# MT9V034.net
KiCad netlist of a schematic drawn in EAGLE
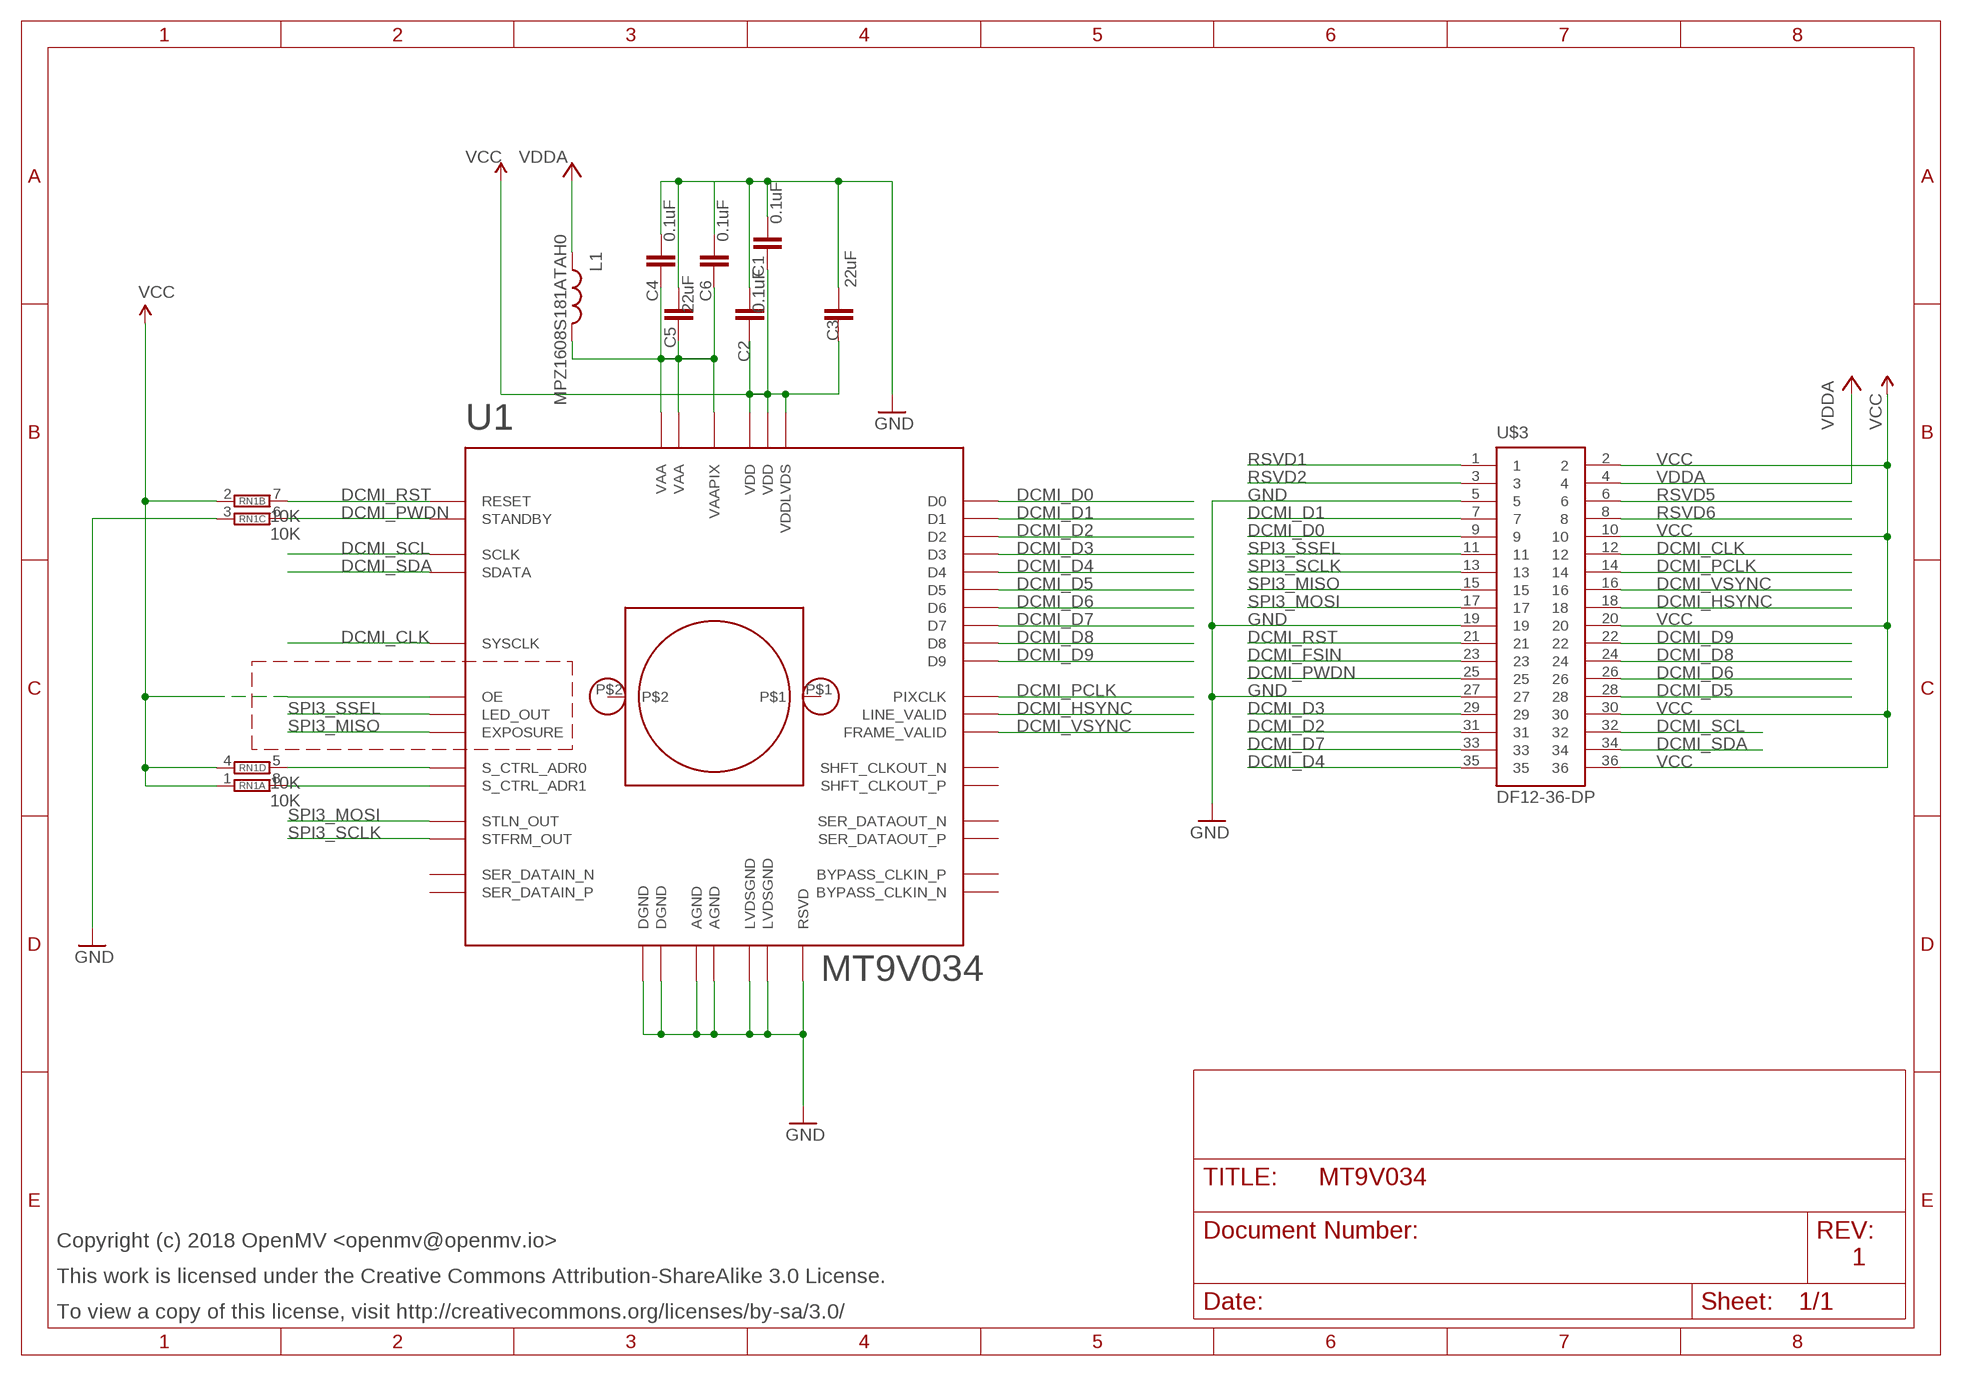
[diagram p0: schematic, sheet 1]

(export (version "E")
  (design (tool "Eeschema 10.0.6"))
  (components
    (comp (ref "C1")
      (value "0.1uF")
      (footprint "eagle-import:0402-CAP")
      (libsource (lib "eagle-import") (part "CAP0402-CAP"))
    )
    (comp (ref "C2")
      (value "0.1uF")
      (footprint "eagle-import:0402-CAP")
      (libsource (lib "eagle-import") (part "CAP0402-CAP"))
    )
    (comp (ref "C3")
      (value "22uF")
      (footprint "eagle-import:0805")
      (libsource (lib "eagle-import") (part "CAP0805"))
    )
    (comp (ref "C4")
      (value "0.1uF")
      (footprint "eagle-import:0402-CAP")
      (libsource (lib "eagle-import") (part "CAP0402-CAP"))
    )
    (comp (ref "C5")
      (value "22uF")
      (footprint "eagle-import:0805")
      (libsource (lib "eagle-import") (part "CAP0805"))
    )
    (comp (ref "C6")
      (value "0.1uF")
      (footprint "eagle-import:0402-CAP")
      (libsource (lib "eagle-import") (part "CAP0402-CAP"))
    )
    (comp (ref "L1")
      (value "MPZ1608S181ATAH0")
      (footprint "eagle-import:0603")
      (libsource (lib "eagle-import") (part "INDUCTOR0603"))
    )
    (comp (ref "LM1")
      (value "LENSMOUNT20MM")
      (footprint "eagle-import:LENSMOUNT-20MM")
      (libsource (lib "eagle-import") (part "LENSMOUNT20MM"))
    )
    (comp (ref "RN1")
      (value "10K")
      (footprint "eagle-import:EXBV8V")
      (fields (field (name "OC_FARNELL") "unknown") (field (name "OC_NEWARK") "unknown"))
      (libsource (lib "eagle-import") (part "4R-NEXBV8V"))
    )
    (comp (ref "U$3")
      (value "DF12-36-DP")
      (footprint "eagle-import:DF12-36-DP")
      (libsource (lib "eagle-import") (part "DF12-36-DP"))
    )
    (comp (ref "U1")
      (value "MT9V034")
      (footprint "eagle-import:CLCC-48")
      (libsource (lib "eagle-import") (part "MT9V032"))
    )
  )
  (nets
    (net (code "1") (name "/DCMI_CLK") (class "Default")
      (node (ref "U$3") (pin "12") (pinfunction "12_12") (pintype "bidirectional"))
      (node (ref "U1") (pin "P$47") (pinfunction "SYSCLK_P$47") (pintype "bidirectional"))
    )
    (net (code "2") (name "/DCMI_D0") (class "Default")
      (node (ref "U$3") (pin "9") (pinfunction "9_9") (pintype "bidirectional"))
      (node (ref "U1") (pin "P$45") (pinfunction "D0_P$45") (pintype "bidirectional"))
    )
    (net (code "3") (name "/DCMI_D1") (class "Default")
      (node (ref "U$3") (pin "7") (pinfunction "7_7") (pintype "bidirectional"))
      (node (ref "U1") (pin "P$44") (pinfunction "D1_P$44") (pintype "bidirectional"))
    )
    (net (code "4") (name "/DCMI_D2") (class "Default")
      (node (ref "U$3") (pin "31") (pinfunction "31_31") (pintype "bidirectional"))
      (node (ref "U1") (pin "P$43") (pinfunction "D2_P$43") (pintype "bidirectional"))
    )
    (net (code "5") (name "/DCMI_D3") (class "Default")
      (node (ref "U$3") (pin "29") (pinfunction "29_29") (pintype "bidirectional"))
      (node (ref "U1") (pin "P$42") (pinfunction "D3_P$42") (pintype "bidirectional"))
    )
    (net (code "6") (name "/DCMI_D4") (class "Default")
      (node (ref "U$3") (pin "35") (pinfunction "35_35") (pintype "bidirectional"))
      (node (ref "U1") (pin "P$41") (pinfunction "D4_P$41") (pintype "bidirectional"))
    )
    (net (code "7") (name "/DCMI_D5") (class "Default")
      (node (ref "U$3") (pin "28") (pinfunction "28_28") (pintype "bidirectional"))
      (node (ref "U1") (pin "P$15") (pinfunction "D5_P$15") (pintype "bidirectional"))
    )
    (net (code "8") (name "/DCMI_D6") (class "Default")
      (node (ref "U$3") (pin "26") (pinfunction "26_26") (pintype "bidirectional"))
      (node (ref "U1") (pin "P$16") (pinfunction "D6_P$16") (pintype "bidirectional"))
    )
    (net (code "9") (name "/DCMI_D7") (class "Default")
      (node (ref "U$3") (pin "33") (pinfunction "33_33") (pintype "bidirectional"))
      (node (ref "U1") (pin "P$17") (pinfunction "D7_P$17") (pintype "bidirectional"))
    )
    (net (code "10") (name "/DCMI_D8") (class "Default")
      (node (ref "U$3") (pin "24") (pinfunction "24_24") (pintype "bidirectional"))
      (node (ref "U1") (pin "P$18") (pinfunction "D8_P$18") (pintype "bidirectional"))
    )
    (net (code "11") (name "/DCMI_D9") (class "Default")
      (node (ref "U$3") (pin "22") (pinfunction "22_22") (pintype "bidirectional"))
      (node (ref "U1") (pin "P$19") (pinfunction "D9_P$19") (pintype "bidirectional"))
    )
    (net (code "12") (name "/DCMI_FSIN") (class "Default")
      (node (ref "U$3") (pin "23") (pinfunction "23_23") (pintype "bidirectional"))
    )
    (net (code "13") (name "/DCMI_HSYNC") (class "Default")
      (node (ref "U$3") (pin "18") (pinfunction "18_18") (pintype "bidirectional"))
      (node (ref "U1") (pin "P$20") (pinfunction "LINE_VALID_P$20") (pintype "bidirectional"))
    )
    (net (code "14") (name "/DCMI_PCLK") (class "Default")
      (node (ref "U$3") (pin "14") (pinfunction "14_14") (pintype "bidirectional"))
      (node (ref "U1") (pin "P$46") (pinfunction "PIXCLK_P$46") (pintype "bidirectional"))
    )
    (net (code "15") (name "/DCMI_PWDN") (class "Default")
      (node (ref "RN1") (pin "6") (pinfunction "2_6") (pintype "passive"))
      (node (ref "U$3") (pin "25") (pinfunction "25_25") (pintype "bidirectional"))
      (node (ref "U1") (pin "P$33") (pinfunction "STANDBY_P$33") (pintype "bidirectional"))
    )
    (net (code "16") (name "/DCMI_RST") (class "Default")
      (node (ref "RN1") (pin "7") (pinfunction "2_7") (pintype "passive"))
      (node (ref "U$3") (pin "21") (pinfunction "21_21") (pintype "bidirectional"))
      (node (ref "U1") (pin "P$32") (pinfunction "RESET_P$32") (pintype "bidirectional"))
    )
    (net (code "17") (name "/DCMI_SCL") (class "Default")
      (node (ref "U$3") (pin "32") (pinfunction "32_32") (pintype "bidirectional"))
      (node (ref "U1") (pin "P$25") (pinfunction "SCLK_P$25") (pintype "bidirectional"))
    )
    (net (code "18") (name "/DCMI_SDA") (class "Default")
      (node (ref "U$3") (pin "34") (pinfunction "34_34") (pintype "bidirectional"))
      (node (ref "U1") (pin "P$24") (pinfunction "SDATA_P$24") (pintype "bidirectional"))
    )
    (net (code "19") (name "/DCMI_VSYNC") (class "Default")
      (node (ref "U$3") (pin "16") (pinfunction "16_16") (pintype "bidirectional"))
      (node (ref "U1") (pin "P$21") (pinfunction "FRAME_VALID_P$21") (pintype "bidirectional"))
    )
    (net (code "20") (name "/P$1") (class "Default")
      (node (ref "LM1") (pin "P$1") (pinfunction "P$1_P$1") (pintype "power_in"))
    )
    (net (code "21") (name "/P$2") (class "Default")
      (node (ref "LM1") (pin "P$2") (pinfunction "P$2_P$2") (pintype "power_in"))
    )
    (net (code "22") (name "/RSVD1") (class "Default")
      (node (ref "U$3") (pin "1") (pinfunction "1_1") (pintype "bidirectional"))
    )
    (net (code "23") (name "/RSVD2") (class "Default")
      (node (ref "U$3") (pin "3") (pinfunction "3_3") (pintype "bidirectional"))
    )
    (net (code "24") (name "/RSVD5") (class "Default")
      (node (ref "U$3") (pin "6") (pinfunction "6_6") (pintype "bidirectional"))
    )
    (net (code "25") (name "/RSVD6") (class "Default")
      (node (ref "U$3") (pin "8") (pinfunction "8_8") (pintype "bidirectional"))
    )
    (net (code "26") (name "/SPI3_MISO") (class "Default")
      (node (ref "U$3") (pin "15") (pinfunction "15_15") (pintype "bidirectional"))
      (node (ref "U1") (pin "P$23") (pinfunction "EXPOSURE_P$23") (pintype "bidirectional"))
    )
    (net (code "27") (name "/SPI3_MOSI") (class "Default")
      (node (ref "U$3") (pin "17") (pinfunction "17_17") (pintype "bidirectional"))
      (node (ref "U1") (pin "P$22") (pinfunction "STLN_OUT_P$22") (pintype "bidirectional"))
    )
    (net (code "28") (name "/SPI3_SCLK") (class "Default")
      (node (ref "U$3") (pin "13") (pinfunction "13_13") (pintype "bidirectional"))
      (node (ref "U1") (pin "P$26") (pinfunction "STFRM_OUT_P$26") (pintype "bidirectional"))
    )
    (net (code "29") (name "/SPI3_SSEL") (class "Default")
      (node (ref "U$3") (pin "11") (pinfunction "11_11") (pintype "bidirectional"))
      (node (ref "U1") (pin "P$27") (pinfunction "LED_OUT_P$27") (pintype "bidirectional"))
    )
    (net (code "30") (name "GND") (class "Default")
      (node (ref "C1") (pin "2") (pinfunction "2_2") (pintype "passive"))
      (node (ref "C2") (pin "2") (pinfunction "2_2") (pintype "passive"))
      (node (ref "C3") (pin "1") (pinfunction "1_1") (pintype "passive"))
      (node (ref "C4") (pin "2") (pinfunction "2_2") (pintype "passive"))
      (node (ref "C5") (pin "1") (pinfunction "1_1") (pintype "passive"))
      (node (ref "C6") (pin "2") (pinfunction "2_2") (pintype "passive"))
      (node (ref "RN1") (pin "3") (pinfunction "1_3") (pintype "passive"))
      (node (ref "U$3") (pin "19") (pinfunction "19_19") (pintype "bidirectional"))
      (node (ref "U$3") (pin "27") (pinfunction "27_27") (pintype "bidirectional"))
      (node (ref "U$3") (pin "5") (pinfunction "5_5") (pintype "bidirectional"))
      (node (ref "U1") (pin "P$12") (pinfunction "LVDSGND_P$12") (pintype "power_in"))
      (node (ref "U1") (pin "P$13") (pinfunction "DGND_P$13") (pintype "power_in"))
      (node (ref "U1") (pin "P$29") (pinfunction "RSVD_P$29") (pintype "power_in"))
      (node (ref "U1") (pin "P$34") (pinfunction "AGND_P$34") (pintype "power_in"))
      (node (ref "U1") (pin "P$38") (pinfunction "AGND_P$38") (pintype "power_in"))
      (node (ref "U1") (pin "P$48") (pinfunction "DGND_P$48") (pintype "power_in"))
      (node (ref "U1") (pin "P$7") (pinfunction "LVDSGND_P$7") (pintype "power_in"))
    )
    (net (code "31") (name "Net-(RN1A-2)") (class "Default")
      (node (ref "RN1") (pin "8") (pinfunction "2_8") (pintype "passive"))
      (node (ref "U1") (pin "P$31") (pinfunction "S_CTRL_ADR1_P$31") (pintype "bidirectional"))
    )
    (net (code "32") (name "Net-(RN1D-2)") (class "Default")
      (node (ref "RN1") (pin "5") (pinfunction "2_5") (pintype "passive"))
      (node (ref "U1") (pin "P$30") (pinfunction "S_CTRL_ADR0_P$30") (pintype "bidirectional"))
    )
    (net (code "33") (name "Net-(U1-VAAPIX)") (class "Default")
      (node (ref "C4") (pin "1") (pinfunction "1_1") (pintype "passive"))
      (node (ref "C5") (pin "2") (pinfunction "2_2") (pintype "passive"))
      (node (ref "C6") (pin "1") (pinfunction "1_1") (pintype "passive"))
      (node (ref "L1") (pin "2") (pinfunction "2_2") (pintype "passive"))
      (node (ref "U1") (pin "P$35") (pinfunction "VAA_P$35") (pintype "power_in"))
      (node (ref "U1") (pin "P$39") (pinfunction "VAA_P$39") (pintype "power_in"))
      (node (ref "U1") (pin "P$40") (pinfunction "VAAPIX_P$40") (pintype "power_in"))
    )
    (net (code "34") (name "VCC") (class "Default")
      (node (ref "C1") (pin "1") (pinfunction "1_1") (pintype "passive"))
      (node (ref "C2") (pin "1") (pinfunction "1_1") (pintype "passive"))
      (node (ref "C3") (pin "2") (pinfunction "2_2") (pintype "passive"))
      (node (ref "RN1") (pin "1") (pinfunction "1_1") (pintype "passive"))
      (node (ref "RN1") (pin "2") (pinfunction "1_2") (pintype "passive"))
      (node (ref "RN1") (pin "4") (pinfunction "1_4") (pintype "passive"))
      (node (ref "U$3") (pin "10") (pinfunction "10_10") (pintype "bidirectional"))
      (node (ref "U$3") (pin "2") (pinfunction "2_2") (pintype "bidirectional"))
      (node (ref "U$3") (pin "20") (pinfunction "20_20") (pintype "bidirectional"))
      (node (ref "U$3") (pin "30") (pinfunction "30_30") (pintype "bidirectional"))
      (node (ref "U$3") (pin "36") (pinfunction "36_36") (pintype "bidirectional"))
      (node (ref "U1") (pin "P$1") (pinfunction "VDD_P$1") (pintype "power_in"))
      (node (ref "U1") (pin "P$14") (pinfunction "VDD_P$14") (pintype "power_in"))
      (node (ref "U1") (pin "P$28") (pinfunction "OE_P$28") (pintype "bidirectional"))
      (node (ref "U1") (pin "P$6") (pinfunction "VDDLVDS_P$6") (pintype "power_in"))
    )
    (net (code "35") (name "VDDA") (class "Default")
      (node (ref "L1") (pin "1") (pinfunction "1_1") (pintype "passive"))
      (node (ref "U$3") (pin "4") (pinfunction "4_4") (pintype "bidirectional"))
    )
    (net (code "36") (name "unconnected-(U1-BYPASS_CLKIN_N-PadP$8)") (class "Default")
      (node (ref "U1") (pin "P$8") (pinfunction "BYPASS_CLKIN_N_P$8") (pintype "bidirectional"))
    )
    (net (code "37") (name "unconnected-(U1-BYPASS_CLKIN_P-PadP$9)") (class "Default")
      (node (ref "U1") (pin "P$9") (pinfunction "BYPASS_CLKIN_P_P$9") (pintype "bidirectional"))
    )
    (net (code "38") (name "unconnected-(U1-SER_DATAIN_N-PadP$10)") (class "Default")
      (node (ref "U1") (pin "P$10") (pinfunction "SER_DATAIN_N_P$10") (pintype "bidirectional"))
    )
    (net (code "39") (name "unconnected-(U1-SER_DATAIN_P-PadP$11)") (class "Default")
      (node (ref "U1") (pin "P$11") (pinfunction "SER_DATAIN_P_P$11") (pintype "bidirectional"))
    )
    (net (code "40") (name "unconnected-(U1-SER_DATAOUT_N-PadP$5)") (class "Default")
      (node (ref "U1") (pin "P$5") (pinfunction "SER_DATAOUT_N_P$5") (pintype "bidirectional"))
    )
    (net (code "41") (name "unconnected-(U1-SER_DATAOUT_P-PadP$4)") (class "Default")
      (node (ref "U1") (pin "P$4") (pinfunction "SER_DATAOUT_P_P$4") (pintype "bidirectional"))
    )
    (net (code "42") (name "unconnected-(U1-SHFT_CLKOUT_N-PadP$2)") (class "Default")
      (node (ref "U1") (pin "P$2") (pinfunction "SHFT_CLKOUT_N_P$2") (pintype "bidirectional"))
    )
    (net (code "43") (name "unconnected-(U1-SHFT_CLKOUT_P-PadP$3)") (class "Default")
      (node (ref "U1") (pin "P$3") (pinfunction "SHFT_CLKOUT_P_P$3") (pintype "bidirectional"))
    )
  )
)
